# sensor10DOF-S.net
KiCad netlist of a schematic drawn in Altium Designer
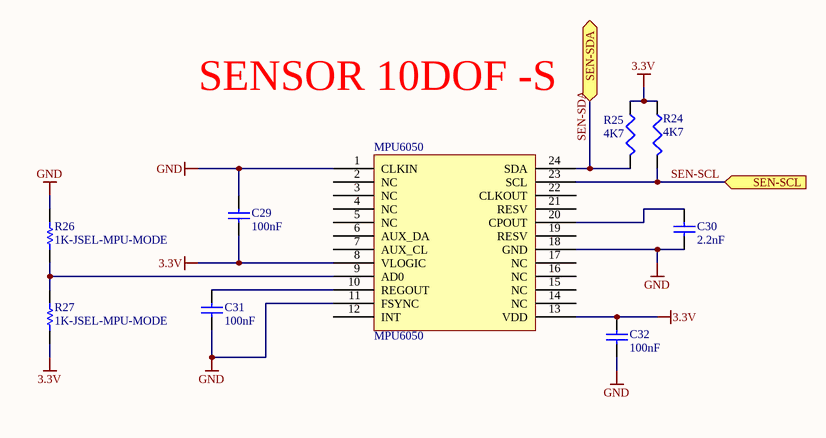
[diagram p0: sensor10DOF-S.SchDoc]

(export (version "E")
  (design (tool "Eeschema 10.0.6"))
  (components
    (comp (ref "C29")
      (value "100nF")
      (footprint "2012[0805]")
      (description "Capacitor")
      (fields (field (name "PUBLISHER") "Altium Limited"))
      (libsource (lib "Miscellaneous Devices") (part "Cap"))
    )
    (comp (ref "C30")
      (value "2.2nF")
      (footprint "2012[0805]")
      (description "Capacitor")
      (fields (field (name "PUBLISHER") "Altium Limited"))
      (libsource (lib "Miscellaneous Devices") (part "Cap"))
    )
    (comp (ref "C31")
      (value "100nF")
      (footprint "2012[0805]")
      (description "Capacitor")
      (fields (field (name "PUBLISHER") "Altium Limited"))
      (libsource (lib "Miscellaneous Devices") (part "Cap"))
    )
    (comp (ref "C32")
      (value "100nF")
      (footprint "2012[0805]")
      (description "Capacitor")
      (fields (field (name "PUBLISHER") "Altium Limited"))
      (libsource (lib "Miscellaneous Devices") (part "Cap"))
    )
    (comp (ref "MPU6050") (value "MPU6050") (footprint "QFN_36") (libsource (lib "m") (part "MPU6050")))
    (comp (ref "R24")
      (value "4K7")
      (footprint "2012[0805]")
      (description "Resistor")
      (fields (field (name "PUBLISHER") "Altium Limited"))
      (libsource (lib "Miscellaneous Devices") (part "Res3"))
    )
    (comp (ref "R25")
      (value "4K7")
      (footprint "2012[0805]")
      (description "Resistor")
      (fields (field (name "PUBLISHER") "Altium Limited"))
      (libsource (lib "Miscellaneous Devices") (part "Res3"))
    )
    (comp (ref "R26")
      (value "1K-JSEL-MPU-MODE")
      (footprint "2012[0805]")
      (description "Resistor")
      (fields (field (name "PUBLISHER") "Altium Limited"))
      (libsource (lib "Miscellaneous Devices") (part "Res1"))
    )
    (comp (ref "R27")
      (value "1K-JSEL-MPU-MODE")
      (footprint "2012[0805]")
      (description "Resistor")
      (fields (field (name "PUBLISHER") "Altium Limited"))
      (libsource (lib "Miscellaneous Devices") (part "Res1"))
    )
  )
  (nets
    (net (code "1") (name "/SEN-SCL") (class "Default")
      (node (ref "MPU6050") (pin "23") (pinfunction "SCL_23") (pintype "passive"))
      (node (ref "R24") (pin "2") (pinfunction "2_2") (pintype "passive"))
    )
    (net (code "2") (name "/SEN-SDA") (class "Default")
      (node (ref "MPU6050") (pin "24") (pinfunction "SDA_24") (pintype "passive"))
      (node (ref "R25") (pin "2") (pinfunction "2_2") (pintype "passive"))
    )
    (net (code "3") (name "3.3V") (class "Default")
      (node (ref "C29") (pin "1") (pinfunction "1_1") (pintype "passive"))
      (node (ref "C32") (pin "2") (pinfunction "2_2") (pintype "passive"))
      (node (ref "MPU6050") (pin "13") (pinfunction "VDD_13") (pintype "passive"))
      (node (ref "MPU6050") (pin "8") (pinfunction "VLOGIC_8") (pintype "passive"))
      (node (ref "R24") (pin "1") (pinfunction "1_1") (pintype "passive"))
      (node (ref "R25") (pin "1") (pinfunction "1_1") (pintype "passive"))
      (node (ref "R27") (pin "1") (pinfunction "1_1") (pintype "passive"))
    )
    (net (code "4") (name "GND") (class "Default")
      (node (ref "C29") (pin "2") (pinfunction "2_2") (pintype "passive"))
      (node (ref "C30") (pin "1") (pinfunction "1_1") (pintype "passive"))
      (node (ref "C31") (pin "1") (pinfunction "1_1") (pintype "passive"))
      (node (ref "C32") (pin "1") (pinfunction "1_1") (pintype "passive"))
      (node (ref "MPU6050") (pin "1") (pinfunction "CLKIN_1") (pintype "passive"))
      (node (ref "MPU6050") (pin "11") (pinfunction "FSYNC_11") (pintype "passive"))
      (node (ref "MPU6050") (pin "18") (pinfunction "GND_18") (pintype "passive"))
      (node (ref "R26") (pin "2") (pinfunction "2_2") (pintype "passive"))
    )
    (net (code "5") (name "Net-(MPU6050-AD0)") (class "Default")
      (node (ref "MPU6050") (pin "9") (pinfunction "AD0_9") (pintype "passive"))
      (node (ref "R26") (pin "1") (pinfunction "1_1") (pintype "passive"))
      (node (ref "R27") (pin "2") (pinfunction "2_2") (pintype "passive"))
    )
    (net (code "6") (name "Net-(MPU6050-CPOUT)") (class "Default")
      (node (ref "C30") (pin "2") (pinfunction "2_2") (pintype "passive"))
      (node (ref "MPU6050") (pin "20") (pinfunction "CPOUT_20") (pintype "passive"))
    )
    (net (code "7") (name "Net-(MPU6050-REGOUT)") (class "Default")
      (node (ref "C31") (pin "2") (pinfunction "2_2") (pintype "passive"))
      (node (ref "MPU6050") (pin "10") (pinfunction "REGOUT_10") (pintype "passive"))
    )
    (net (code "8") (name "unconnected-(MPU6050-AUX_CL-Pad7)") (class "Default")
      (node (ref "MPU6050") (pin "7") (pinfunction "AUX_CL_7") (pintype "passive"))
    )
    (net (code "9") (name "unconnected-(MPU6050-AUX_DA-Pad6)") (class "Default")
      (node (ref "MPU6050") (pin "6") (pinfunction "AUX_DA_6") (pintype "passive"))
    )
    (net (code "10") (name "unconnected-(MPU6050-CLKOUT-Pad22)") (class "Default")
      (node (ref "MPU6050") (pin "22") (pinfunction "CLKOUT_22") (pintype "passive"))
    )
    (net (code "11") (name "unconnected-(MPU6050-INT-Pad12)") (class "Default")
      (node (ref "MPU6050") (pin "12") (pinfunction "INT_12") (pintype "passive"))
    )
    (net (code "12") (name "unconnected-(MPU6050-NC-Pad2)") (class "Default")
      (node (ref "MPU6050") (pin "2") (pinfunction "NC_2") (pintype "passive"))
    )
    (net (code "13") (name "unconnected-(MPU6050-NC-Pad3)") (class "Default")
      (node (ref "MPU6050") (pin "3") (pinfunction "NC_3") (pintype "passive"))
    )
    (net (code "14") (name "unconnected-(MPU6050-NC-Pad4)") (class "Default")
      (node (ref "MPU6050") (pin "4") (pinfunction "NC_4") (pintype "passive"))
    )
    (net (code "15") (name "unconnected-(MPU6050-NC-Pad5)") (class "Default")
      (node (ref "MPU6050") (pin "5") (pinfunction "NC_5") (pintype "passive"))
    )
    (net (code "16") (name "unconnected-(MPU6050-NC-Pad14)") (class "Default")
      (node (ref "MPU6050") (pin "14") (pinfunction "NC_14") (pintype "passive"))
    )
    (net (code "17") (name "unconnected-(MPU6050-NC-Pad15)") (class "Default")
      (node (ref "MPU6050") (pin "15") (pinfunction "NC_15") (pintype "passive"))
    )
    (net (code "18") (name "unconnected-(MPU6050-NC-Pad16)") (class "Default")
      (node (ref "MPU6050") (pin "16") (pinfunction "NC_16") (pintype "passive"))
    )
    (net (code "19") (name "unconnected-(MPU6050-NC-Pad17)") (class "Default")
      (node (ref "MPU6050") (pin "17") (pinfunction "NC_17") (pintype "passive"))
    )
    (net (code "20") (name "unconnected-(MPU6050-RESV-Pad19)") (class "Default")
      (node (ref "MPU6050") (pin "19") (pinfunction "RESV_19") (pintype "passive"))
    )
    (net (code "21") (name "unconnected-(MPU6050-RESV-Pad21)") (class "Default")
      (node (ref "MPU6050") (pin "21") (pinfunction "RESV_21") (pintype "passive"))
    )
  )
)
